# Controlador_PID_Analogico.net
KiCad netlist of a schematic drawn in EAGLE
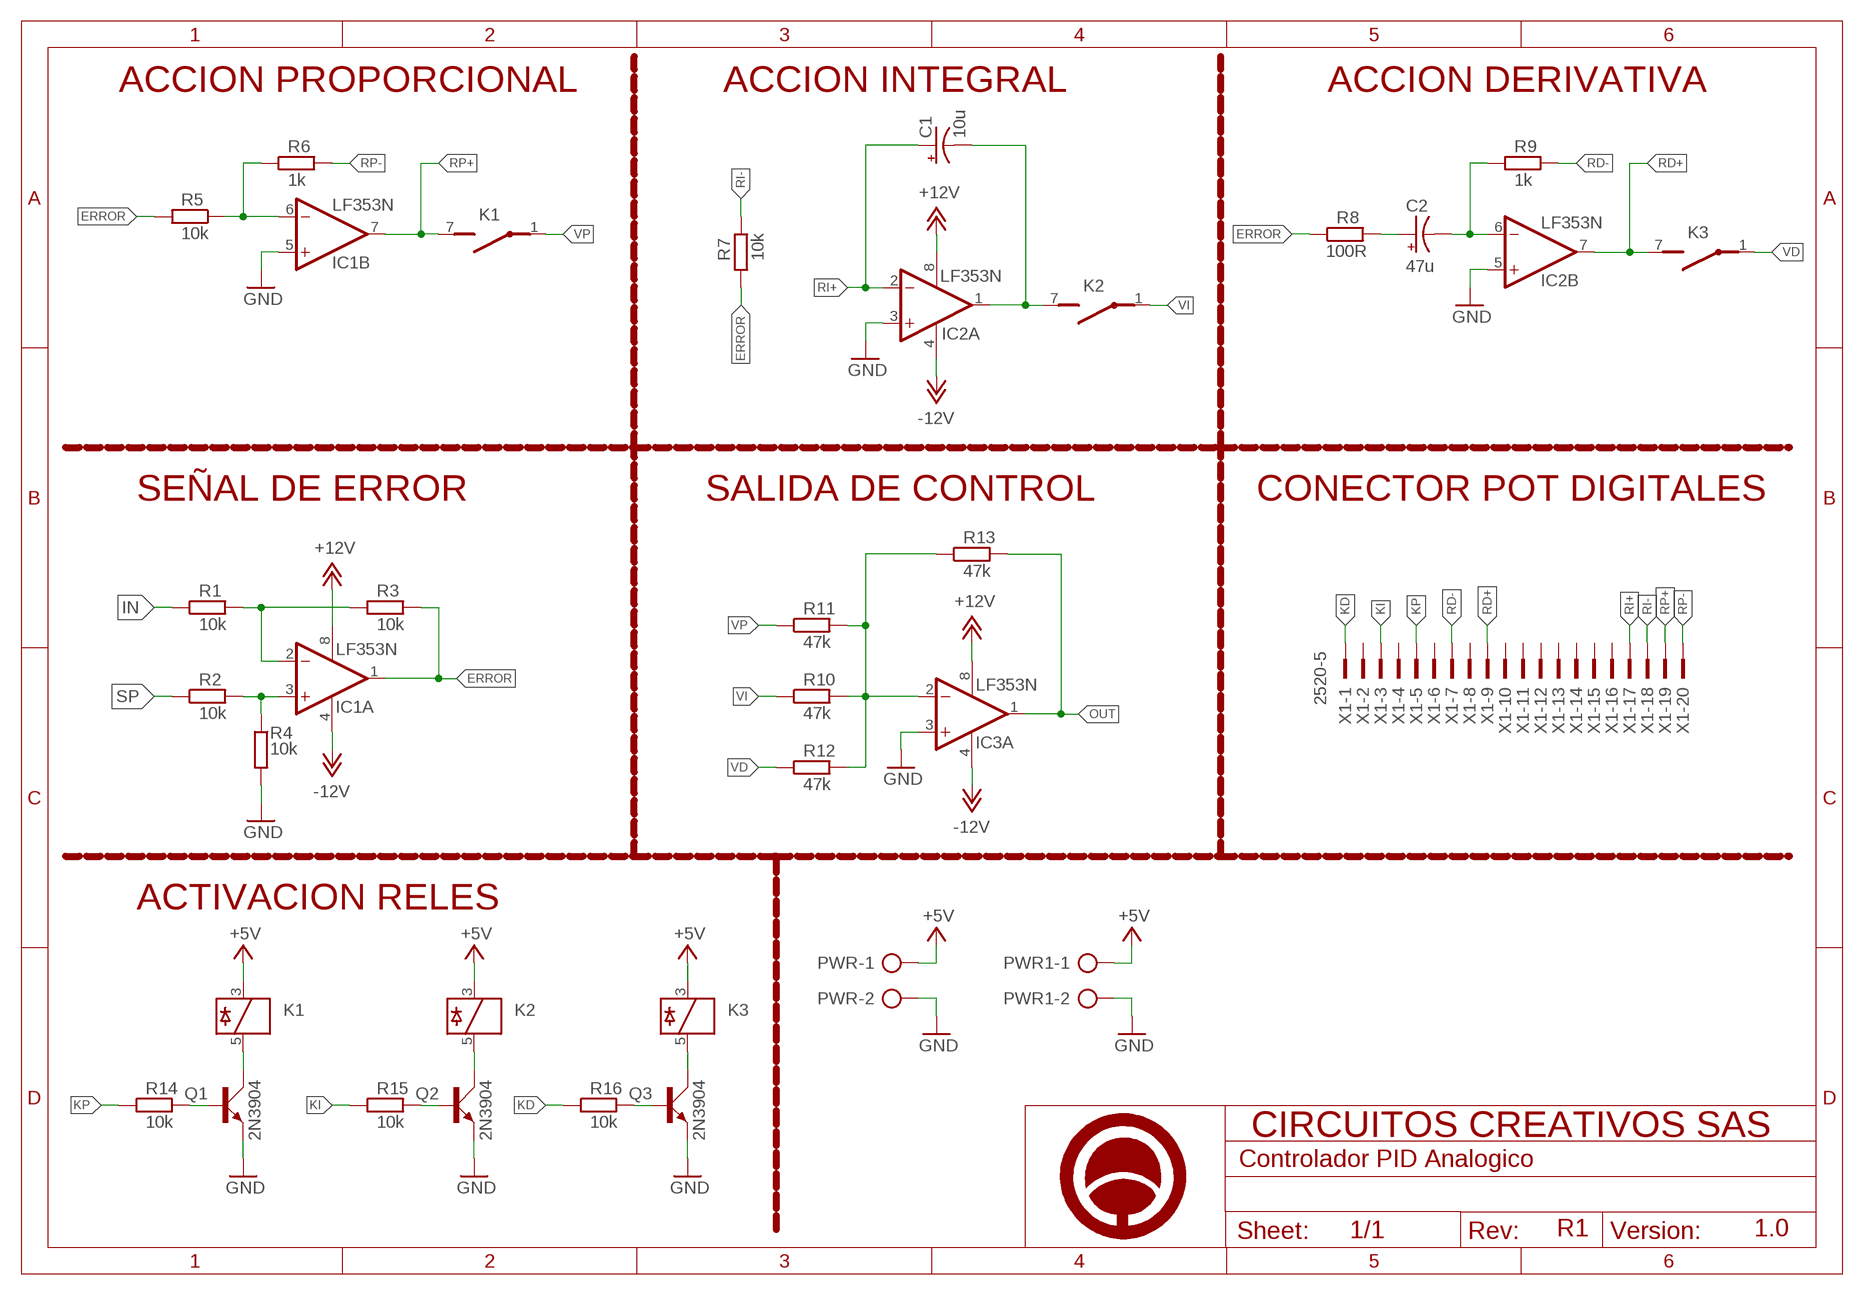
[diagram p0: schematic, sheet 1]

(export (version "E")
  (design (tool "Eeschema 10.0.6"))
  (components
    (comp (ref "C1")
      (value "10u")
      (footprint "eagle-import:E2,5-6E")
      (libsource (lib "eagle-import") (part "CPOL-USE2,5-6E"))
    )
    (comp (ref "C2")
      (value "47u")
      (footprint "eagle-import:E2,5-6E")
      (libsource (lib "eagle-import") (part "CPOL-USE2,5-6E"))
    )
    (comp (ref "IC1")
      (value "LF353N")
      (footprint "eagle-import:DIL08")
      (libsource (lib "eagle-import") (part "LF353N"))
    )
    (comp (ref "IC2")
      (value "LF353N")
      (footprint "eagle-import:DIL08")
      (libsource (lib "eagle-import") (part "LF353N"))
    )
    (comp (ref "IC3")
      (value "LF353N")
      (footprint "eagle-import:DIL08")
      (libsource (lib "eagle-import") (part "LF353N"))
    )
    (comp (ref "K1")
      (value "35701331")
      (footprint "eagle-import:REED")
      (libsource (lib "eagle-import") (part "35701331"))
    )
    (comp (ref "K2")
      (value "35701331")
      (footprint "eagle-import:REED")
      (libsource (lib "eagle-import") (part "35701331"))
    )
    (comp (ref "K3")
      (value "35701331")
      (footprint "eagle-import:REED")
      (libsource (lib "eagle-import") (part "35701331"))
    )
    (comp (ref "PWR")
      (value "AK500/2")
      (footprint "eagle-import:AK500_2")
      (libsource (lib "eagle-import") (part "AK500/2"))
    )
    (comp (ref "PWR1")
      (value "AK500/2")
      (footprint "eagle-import:AK500_2")
      (libsource (lib "eagle-import") (part "AK500/2"))
    )
    (comp (ref "Q1")
      (value "2N3904")
      (footprint "eagle-import:TO92D")
      (libsource (lib "eagle-import") (part "2N3904"))
    )
    (comp (ref "Q2")
      (value "2N3904")
      (footprint "eagle-import:TO92D")
      (libsource (lib "eagle-import") (part "2N3904"))
    )
    (comp (ref "Q3")
      (value "2N3904")
      (footprint "eagle-import:TO92D")
      (libsource (lib "eagle-import") (part "2N3904"))
    )
    (comp (ref "R1")
      (value "10k")
      (footprint "eagle-import:0204_7")
      (libsource (lib "eagle-import") (part "R-EU_0204/7"))
    )
    (comp (ref "R2")
      (value "10k")
      (footprint "eagle-import:0204_7")
      (libsource (lib "eagle-import") (part "R-EU_0204/7"))
    )
    (comp (ref "R3")
      (value "10k")
      (footprint "eagle-import:0204_7")
      (libsource (lib "eagle-import") (part "R-EU_0204/7"))
    )
    (comp (ref "R4")
      (value "10k")
      (footprint "eagle-import:0204_7")
      (libsource (lib "eagle-import") (part "R-EU_0204/7"))
    )
    (comp (ref "R5")
      (value "10k")
      (footprint "eagle-import:0204_7")
      (libsource (lib "eagle-import") (part "R-EU_0204/7"))
    )
    (comp (ref "R6")
      (value "1k")
      (footprint "eagle-import:0204_7")
      (libsource (lib "eagle-import") (part "R-EU_0204/7"))
    )
    (comp (ref "R7")
      (value "10k")
      (footprint "eagle-import:0204_7")
      (libsource (lib "eagle-import") (part "R-EU_0204/7"))
    )
    (comp (ref "R8")
      (value "100R")
      (footprint "eagle-import:0204_7")
      (libsource (lib "eagle-import") (part "R-EU_0204/7"))
    )
    (comp (ref "R9")
      (value "1k")
      (footprint "eagle-import:0204_7")
      (libsource (lib "eagle-import") (part "R-EU_0204/7"))
    )
    (comp (ref "R10")
      (value "47k")
      (footprint "eagle-import:0204_7")
      (libsource (lib "eagle-import") (part "R-EU_0204/7"))
    )
    (comp (ref "R11")
      (value "47k")
      (footprint "eagle-import:0204_7")
      (libsource (lib "eagle-import") (part "R-EU_0204/7"))
    )
    (comp (ref "R12")
      (value "47k")
      (footprint "eagle-import:0204_7")
      (libsource (lib "eagle-import") (part "R-EU_0204/7"))
    )
    (comp (ref "R13")
      (value "47k")
      (footprint "eagle-import:0204_7")
      (libsource (lib "eagle-import") (part "R-EU_0204/7"))
    )
    (comp (ref "R14")
      (value "10k")
      (footprint "eagle-import:0204_7")
      (libsource (lib "eagle-import") (part "R-EU_0204/7"))
    )
    (comp (ref "R15")
      (value "10k")
      (footprint "eagle-import:0204_7")
      (libsource (lib "eagle-import") (part "R-EU_0204/7"))
    )
    (comp (ref "R16")
      (value "10k")
      (footprint "eagle-import:0204_7")
      (libsource (lib "eagle-import") (part "R-EU_0204/7"))
    )
    (comp (ref "U$1")
      (value "A4_HORIZONTAL")
      (footprint "eagle-import:LOGO")
      (libsource (lib "eagle-import") (part "A4_HORIZONTAL"))
    )
    (comp (ref "X1")
      (value "2520-5")
      (footprint "eagle-import:PAK100_2500-5-20")
      (fields (field (name "MPN") "D2520-5002-AR"))
      (libsource (lib "eagle-import") (part "2520-5"))
    )
  )
  (nets
    (net (code "1") (name "+5V") (class "Default")
      (node (ref "K1") (pin "3") (pinfunction "3_3") (pintype "passive"))
      (node (ref "K2") (pin "3") (pinfunction "3_3") (pintype "passive"))
      (node (ref "K3") (pin "3") (pinfunction "3_3") (pintype "passive"))
      (node (ref "PWR") (pin "1") (pinfunction "KL_1") (pintype "passive"))
      (node (ref "PWR1") (pin "1") (pinfunction "KL_1") (pintype "passive"))
    )
    (net (code "2") (name "+12V") (class "Default")
      (node (ref "IC1") (pin "8") (pinfunction "V+_8") (pintype "power_in"))
      (node (ref "IC2") (pin "8") (pinfunction "V+_8") (pintype "power_in"))
      (node (ref "IC3") (pin "8") (pinfunction "V+_8") (pintype "power_in"))
    )
    (net (code "3") (name "-12V") (class "Default")
      (node (ref "IC1") (pin "4") (pinfunction "V-_4") (pintype "power_in"))
      (node (ref "IC2") (pin "4") (pinfunction "V-_4") (pintype "power_in"))
      (node (ref "IC3") (pin "4") (pinfunction "V-_4") (pintype "power_in"))
    )
    (net (code "4") (name "ERROR") (class "Default")
      (node (ref "IC1") (pin "1") (pinfunction "OUT_1") (pintype "output"))
      (node (ref "R3") (pin "2") (pinfunction "2_2") (pintype "passive"))
      (node (ref "R5") (pin "2") (pinfunction "2_2") (pintype "passive"))
      (node (ref "R7") (pin "2") (pinfunction "2_2") (pintype "passive"))
      (node (ref "R8") (pin "1") (pinfunction "1_1") (pintype "passive"))
    )
    (net (code "5") (name "GND") (class "Default")
      (node (ref "IC1") (pin "5") (pinfunction "+IN_5") (pintype "input"))
      (node (ref "IC2") (pin "3") (pinfunction "+IN_3") (pintype "input"))
      (node (ref "IC2") (pin "5") (pinfunction "+IN_5") (pintype "input"))
      (node (ref "IC3") (pin "3") (pinfunction "+IN_3") (pintype "input"))
      (node (ref "PWR") (pin "2") (pinfunction "KL_2") (pintype "passive"))
      (node (ref "PWR1") (pin "2") (pinfunction "KL_2") (pintype "passive"))
      (node (ref "Q1") (pin "E") (pinfunction "E_E") (pintype "passive"))
      (node (ref "Q2") (pin "E") (pinfunction "E_E") (pintype "passive"))
      (node (ref "Q3") (pin "E") (pinfunction "E_E") (pintype "passive"))
      (node (ref "R4") (pin "2") (pinfunction "2_2") (pintype "passive"))
    )
    (net (code "6") (name "IN") (class "Default")
      (node (ref "R1") (pin "1") (pinfunction "1_1") (pintype "passive"))
    )
    (net (code "7") (name "KD") (class "Default")
      (node (ref "R16") (pin "1") (pinfunction "1_1") (pintype "passive"))
      (node (ref "X1") (pin "1") (pinfunction "KL_1") (pintype "passive"))
    )
    (net (code "8") (name "KI") (class "Default")
      (node (ref "R15") (pin "1") (pinfunction "1_1") (pintype "passive"))
      (node (ref "X1") (pin "3") (pinfunction "KL_3") (pintype "passive"))
    )
    (net (code "9") (name "KP") (class "Default")
      (node (ref "R14") (pin "1") (pinfunction "1_1") (pintype "passive"))
      (node (ref "X1") (pin "5") (pinfunction "KL_5") (pintype "passive"))
    )
    (net (code "10") (name "Net-(C2-Pad+)") (class "Default")
      (node (ref "C2") (pin "+") (pinfunction "+_+") (pintype "passive"))
      (node (ref "R8") (pin "2") (pinfunction "2_2") (pintype "passive"))
    )
    (net (code "11") (name "Net-(IC1A-+IN)") (class "Default")
      (node (ref "IC1") (pin "3") (pinfunction "+IN_3") (pintype "input"))
      (node (ref "R2") (pin "2") (pinfunction "2_2") (pintype "passive"))
      (node (ref "R4") (pin "1") (pinfunction "1_1") (pintype "passive"))
    )
    (net (code "12") (name "Net-(IC1A--IN)") (class "Default")
      (node (ref "IC1") (pin "2") (pinfunction "-IN_2") (pintype "input"))
      (node (ref "R1") (pin "2") (pinfunction "2_2") (pintype "passive"))
      (node (ref "R3") (pin "1") (pinfunction "1_1") (pintype "passive"))
    )
    (net (code "13") (name "Net-(IC1B--IN)") (class "Default")
      (node (ref "IC1") (pin "6") (pinfunction "-IN_6") (pintype "input"))
      (node (ref "R5") (pin "1") (pinfunction "1_1") (pintype "passive"))
      (node (ref "R6") (pin "1") (pinfunction "1_1") (pintype "passive"))
    )
    (net (code "14") (name "Net-(IC2A-OUT)") (class "Default")
      (node (ref "C1") (pin "-") (pinfunction "-_-") (pintype "passive"))
      (node (ref "IC2") (pin "1") (pinfunction "OUT_1") (pintype "output"))
      (node (ref "K2") (pin "7") (pinfunction "S_7") (pintype "passive"))
    )
    (net (code "15") (name "Net-(IC2B--IN)") (class "Default")
      (node (ref "C2") (pin "-") (pinfunction "-_-") (pintype "passive"))
      (node (ref "IC2") (pin "6") (pinfunction "-IN_6") (pintype "input"))
      (node (ref "R9") (pin "1") (pinfunction "1_1") (pintype "passive"))
    )
    (net (code "16") (name "Net-(IC3A--IN)") (class "Default")
      (node (ref "IC3") (pin "2") (pinfunction "-IN_2") (pintype "input"))
      (node (ref "R10") (pin "2") (pinfunction "2_2") (pintype "passive"))
      (node (ref "R11") (pin "2") (pinfunction "2_2") (pintype "passive"))
      (node (ref "R12") (pin "2") (pinfunction "2_2") (pintype "passive"))
      (node (ref "R13") (pin "1") (pinfunction "1_1") (pintype "passive"))
    )
    (net (code "17") (name "Net-(K1-Pad5)") (class "Default")
      (node (ref "K1") (pin "5") (pinfunction "5_5") (pintype "passive"))
      (node (ref "Q1") (pin "C") (pinfunction "C_C") (pintype "passive"))
    )
    (net (code "18") (name "Net-(K2-Pad5)") (class "Default")
      (node (ref "K2") (pin "5") (pinfunction "5_5") (pintype "passive"))
      (node (ref "Q2") (pin "C") (pinfunction "C_C") (pintype "passive"))
    )
    (net (code "19") (name "Net-(K3-Pad5)") (class "Default")
      (node (ref "K3") (pin "5") (pinfunction "5_5") (pintype "passive"))
      (node (ref "Q3") (pin "C") (pinfunction "C_C") (pintype "passive"))
    )
    (net (code "20") (name "Net-(Q1-PadB)") (class "Default")
      (node (ref "Q1") (pin "B") (pinfunction "B_B") (pintype "passive"))
      (node (ref "R14") (pin "2") (pinfunction "2_2") (pintype "passive"))
    )
    (net (code "21") (name "Net-(Q2-PadB)") (class "Default")
      (node (ref "Q2") (pin "B") (pinfunction "B_B") (pintype "passive"))
      (node (ref "R15") (pin "2") (pinfunction "2_2") (pintype "passive"))
    )
    (net (code "22") (name "Net-(Q3-PadB)") (class "Default")
      (node (ref "Q3") (pin "B") (pinfunction "B_B") (pintype "passive"))
      (node (ref "R16") (pin "2") (pinfunction "2_2") (pintype "passive"))
    )
    (net (code "23") (name "OUT") (class "Default")
      (node (ref "IC3") (pin "1") (pinfunction "OUT_1") (pintype "output"))
      (node (ref "R13") (pin "2") (pinfunction "2_2") (pintype "passive"))
    )
    (net (code "24") (name "RD+") (class "Default")
      (node (ref "IC2") (pin "7") (pinfunction "OUT_7") (pintype "output"))
      (node (ref "K3") (pin "7") (pinfunction "S_7") (pintype "passive"))
      (node (ref "X1") (pin "9") (pinfunction "KL_9") (pintype "passive"))
    )
    (net (code "25") (name "RD-") (class "Default")
      (node (ref "R9") (pin "2") (pinfunction "2_2") (pintype "passive"))
      (node (ref "X1") (pin "7") (pinfunction "KL_7") (pintype "passive"))
    )
    (net (code "26") (name "RI+") (class "Default")
      (node (ref "C1") (pin "+") (pinfunction "+_+") (pintype "passive"))
      (node (ref "IC2") (pin "2") (pinfunction "-IN_2") (pintype "input"))
      (node (ref "X1") (pin "17") (pinfunction "KL_17") (pintype "passive"))
    )
    (net (code "27") (name "RI-") (class "Default")
      (node (ref "R7") (pin "1") (pinfunction "1_1") (pintype "passive"))
      (node (ref "X1") (pin "18") (pinfunction "KL_18") (pintype "passive"))
    )
    (net (code "28") (name "RP+") (class "Default")
      (node (ref "IC1") (pin "7") (pinfunction "OUT_7") (pintype "output"))
      (node (ref "K1") (pin "7") (pinfunction "S_7") (pintype "passive"))
      (node (ref "X1") (pin "19") (pinfunction "KL_19") (pintype "passive"))
    )
    (net (code "29") (name "RP-") (class "Default")
      (node (ref "R6") (pin "2") (pinfunction "2_2") (pintype "passive"))
      (node (ref "X1") (pin "20") (pinfunction "KL_20") (pintype "passive"))
    )
    (net (code "30") (name "SP") (class "Default")
      (node (ref "R2") (pin "1") (pinfunction "1_1") (pintype "passive"))
    )
    (net (code "31") (name "VD") (class "Default")
      (node (ref "K3") (pin "1") (pinfunction "P_1") (pintype "passive"))
      (node (ref "R12") (pin "1") (pinfunction "1_1") (pintype "passive"))
    )
    (net (code "32") (name "VI") (class "Default")
      (node (ref "K2") (pin "1") (pinfunction "P_1") (pintype "passive"))
      (node (ref "R10") (pin "1") (pinfunction "1_1") (pintype "passive"))
    )
    (net (code "33") (name "VP") (class "Default")
      (node (ref "K1") (pin "1") (pinfunction "P_1") (pintype "passive"))
      (node (ref "R11") (pin "1") (pinfunction "1_1") (pintype "passive"))
    )
    (net (code "34") (name "unconnected-(X1B-KL-Pad10)") (class "Default")
      (node (ref "X1") (pin "10") (pinfunction "KL_10") (pintype "passive"))
    )
    (net (code "35") (name "unconnected-(X1C-KL-Pad11)") (class "Default")
      (node (ref "X1") (pin "11") (pinfunction "KL_11") (pintype "passive"))
    )
    (net (code "36") (name "unconnected-(X1D-KL-Pad12)") (class "Default")
      (node (ref "X1") (pin "12") (pinfunction "KL_12") (pintype "passive"))
    )
    (net (code "37") (name "unconnected-(X1E-KL-Pad13)") (class "Default")
      (node (ref "X1") (pin "13") (pinfunction "KL_13") (pintype "passive"))
    )
    (net (code "38") (name "unconnected-(X1F-KL-Pad14)") (class "Default")
      (node (ref "X1") (pin "14") (pinfunction "KL_14") (pintype "passive"))
    )
    (net (code "39") (name "unconnected-(X1G-KL-Pad15)") (class "Default")
      (node (ref "X1") (pin "15") (pinfunction "KL_15") (pintype "passive"))
    )
    (net (code "40") (name "unconnected-(X1H-KL-Pad16)") (class "Default")
      (node (ref "X1") (pin "16") (pinfunction "KL_16") (pintype "passive"))
    )
    (net (code "41") (name "unconnected-(X1L-KL-Pad2)") (class "Default")
      (node (ref "X1") (pin "2") (pinfunction "KL_2") (pintype "passive"))
    )
    (net (code "42") (name "unconnected-(X1O-KL-Pad4)") (class "Default")
      (node (ref "X1") (pin "4") (pinfunction "KL_4") (pintype "passive"))
    )
    (net (code "43") (name "unconnected-(X1Q-KL-Pad6)") (class "Default")
      (node (ref "X1") (pin "6") (pinfunction "KL_6") (pintype "passive"))
    )
    (net (code "44") (name "unconnected-(X1S-KL-Pad8)") (class "Default")
      (node (ref "X1") (pin "8") (pinfunction "KL_8") (pintype "passive"))
    )
  )
)
